# PCI_short_card_universal_-_32_BIT-4.net
KiCad netlist of a schematic drawn in Altium Designer
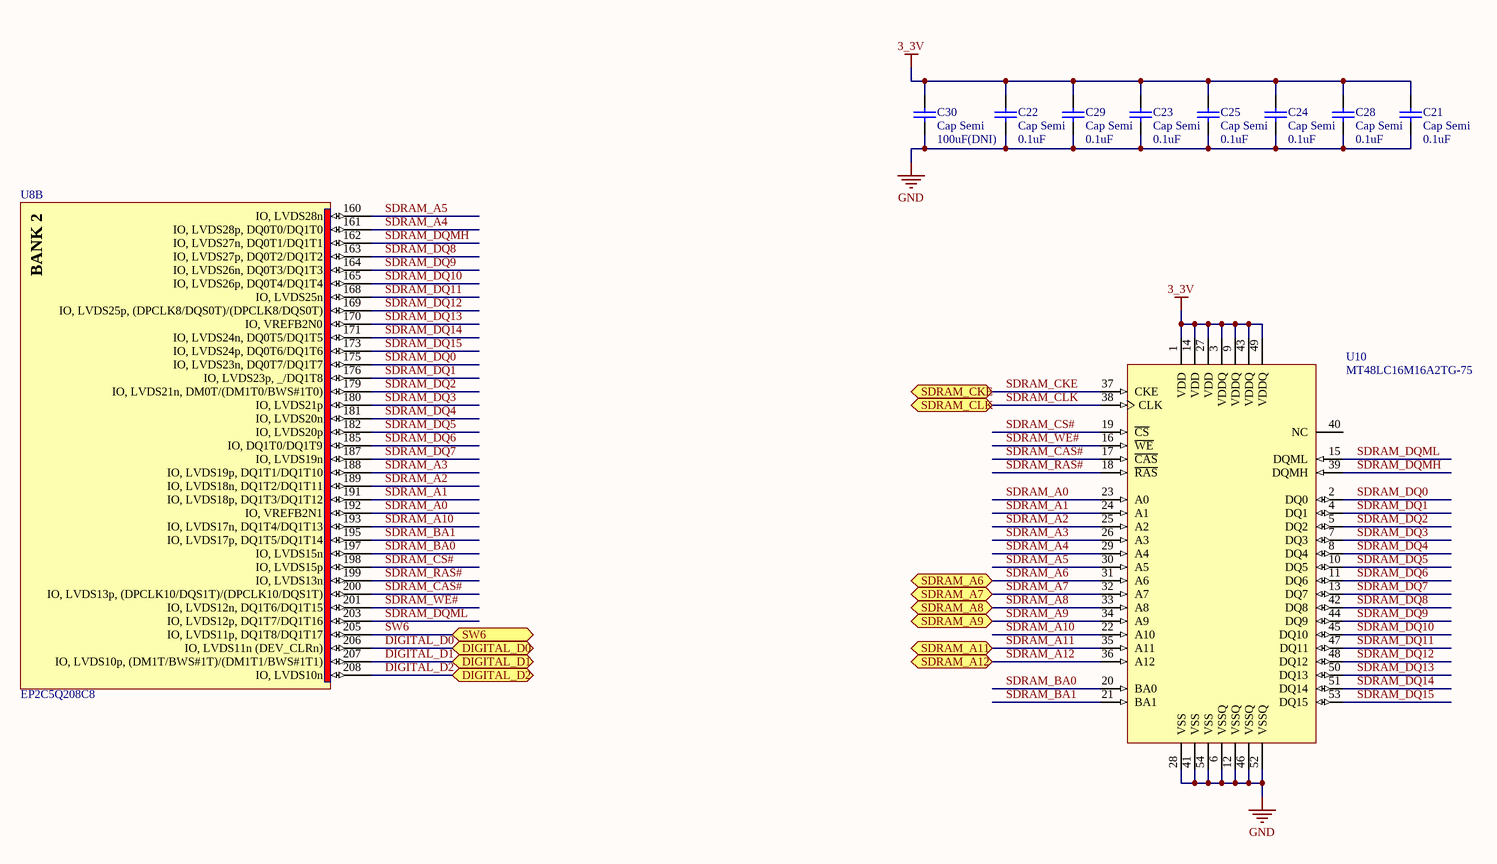
[diagram p0: PCI short card universal - 32 BIT-4.schdoc]

(export (version "E")
  (design (tool "Eeschema 10.0.6"))
  (components
    (comp (ref "C21")
      (value "Cap Semi")
      (footprint "RESC1608N")
      (description "Capacitor (Semiconductor SIM Model)")
      (fields (field (name "ALTIUM_VALUE") "0.1uF") (field (name "PUBLISHER") "Altium Limited"))
      (libsource (lib "Miscellaneous Devices") (part "Cap Semi"))
    )
    (comp (ref "C22")
      (value "Cap Semi")
      (footprint "RESC1608N")
      (description "Capacitor (Semiconductor SIM Model)")
      (fields (field (name "ALTIUM_VALUE") "0.1uF") (field (name "PUBLISHER") "Altium Limited"))
      (libsource (lib "Miscellaneous Devices") (part "Cap Semi"))
    )
    (comp (ref "C23")
      (value "Cap Semi")
      (footprint "RESC1608N")
      (description "Capacitor (Semiconductor SIM Model)")
      (fields (field (name "ALTIUM_VALUE") "0.1uF") (field (name "PUBLISHER") "Altium Limited"))
      (libsource (lib "Miscellaneous Devices") (part "Cap Semi"))
    )
    (comp (ref "C24")
      (value "Cap Semi")
      (footprint "RESC1608N")
      (description "Capacitor (Semiconductor SIM Model)")
      (fields (field (name "ALTIUM_VALUE") "0.1uF") (field (name "PUBLISHER") "Altium Limited"))
      (libsource (lib "Miscellaneous Devices") (part "Cap Semi"))
    )
    (comp (ref "C25")
      (value "Cap Semi")
      (footprint "RESC1608N")
      (description "Capacitor (Semiconductor SIM Model)")
      (fields (field (name "ALTIUM_VALUE") "0.1uF") (field (name "PUBLISHER") "Altium Limited"))
      (libsource (lib "Miscellaneous Devices") (part "Cap Semi"))
    )
    (comp (ref "C28")
      (value "Cap Semi")
      (footprint "RESC1608N")
      (description "Capacitor (Semiconductor SIM Model)")
      (fields (field (name "ALTIUM_VALUE") "0.1uF") (field (name "PUBLISHER") "Altium Limited"))
      (libsource (lib "Miscellaneous Devices") (part "Cap Semi"))
    )
    (comp (ref "C29")
      (value "Cap Semi")
      (footprint "RESC1608N")
      (description "Capacitor (Semiconductor SIM Model)")
      (fields (field (name "ALTIUM_VALUE") "0.1uF") (field (name "PUBLISHER") "Altium Limited"))
      (libsource (lib "Miscellaneous Devices") (part "Cap Semi"))
    )
    (comp (ref "C30")
      (value "Cap Semi")
      (footprint "CD3225-1210")
      (description "Capacitor (Semiconductor SIM Model)")
      (fields (field (name "ALTIUM_VALUE") "100uF(DNI)") (field (name "PUBLISHER") "Altium Limited"))
      (libsource (lib "Miscellaneous Devices") (part "Cap Semi"))
    )
    (comp (ref "U8")
      (value "EP2C5Q208C8")
      (footprint "PQFP208_N")
      (fields (field (name "PUBLISHER") "Altium Limited"))
      (libsource (lib "Altera Cyclone II") (part "EP2C5Q208C8"))
    )
    (comp (ref "U10")
      (value "MT48LC16M16A2TG-75")
      (footprint "TSOP2-54_M")
      (description "MICRON")
      (fields (field (name "PUBLISHER") "Altium Limited"))
      (libsource (lib "Micron Memory Dynamic RAM") (part "MT48LC16M16A2TG-75"))
    )
  )
  (nets
    (net (code "1") (name "/DIGITAL_D0") (class "Default")
      (node (ref "U8") (pin "206") (pinfunction "IO,_LVDS11n_(DEV_CLRn)_206") (pintype "bidirectional"))
    )
    (net (code "2") (name "/DIGITAL_D1") (class "Default")
      (node (ref "U8") (pin "207") (pinfunction "IO,_LVDS10p,_(DM1T/BWS#1T)/(DM1T1/BWS#1T1)_207") (pintype "bidirectional"))
    )
    (net (code "3") (name "/DIGITAL_D2") (class "Default")
      (node (ref "U8") (pin "208") (pinfunction "IO,_LVDS10n_208") (pintype "bidirectional"))
    )
    (net (code "4") (name "/SDRAM_A0") (class "Default")
      (node (ref "U10") (pin "23") (pinfunction "A0_23") (pintype "input"))
      (node (ref "U8") (pin "192") (pinfunction "IO,_VREFB2N1_192") (pintype "bidirectional"))
    )
    (net (code "5") (name "/SDRAM_A1") (class "Default")
      (node (ref "U10") (pin "24") (pinfunction "A1_24") (pintype "input"))
      (node (ref "U8") (pin "191") (pinfunction "IO,_LVDS18p,_DQ1T3/DQ1T12_191") (pintype "bidirectional"))
    )
    (net (code "6") (name "/SDRAM_A2") (class "Default")
      (node (ref "U10") (pin "25") (pinfunction "A2_25") (pintype "input"))
      (node (ref "U8") (pin "189") (pinfunction "IO,_LVDS18n,_DQ1T2/DQ1T11_189") (pintype "bidirectional"))
    )
    (net (code "7") (name "/SDRAM_A3") (class "Default")
      (node (ref "U10") (pin "26") (pinfunction "A3_26") (pintype "input"))
      (node (ref "U8") (pin "188") (pinfunction "IO,_LVDS19p,_DQ1T1/DQ1T10_188") (pintype "bidirectional"))
    )
    (net (code "8") (name "/SDRAM_A4") (class "Default")
      (node (ref "U10") (pin "29") (pinfunction "A4_29") (pintype "input"))
      (node (ref "U8") (pin "161") (pinfunction "IO,_LVDS28p,_DQ0T0/DQ1T0_161") (pintype "bidirectional"))
    )
    (net (code "9") (name "/SDRAM_A5") (class "Default")
      (node (ref "U10") (pin "30") (pinfunction "A5_30") (pintype "input"))
      (node (ref "U8") (pin "160") (pinfunction "IO,_LVDS28n_160") (pintype "bidirectional"))
    )
    (net (code "10") (name "/SDRAM_A6") (class "Default")
      (node (ref "U10") (pin "31") (pinfunction "A6_31") (pintype "input"))
    )
    (net (code "11") (name "/SDRAM_A7") (class "Default")
      (node (ref "U10") (pin "32") (pinfunction "A7_32") (pintype "input"))
    )
    (net (code "12") (name "/SDRAM_A8") (class "Default")
      (node (ref "U10") (pin "33") (pinfunction "A8_33") (pintype "input"))
    )
    (net (code "13") (name "/SDRAM_A9") (class "Default")
      (node (ref "U10") (pin "34") (pinfunction "A9_34") (pintype "input"))
    )
    (net (code "14") (name "/SDRAM_A10") (class "Default")
      (node (ref "U10") (pin "22") (pinfunction "A10_22") (pintype "input"))
      (node (ref "U8") (pin "193") (pinfunction "IO,_LVDS17n,_DQ1T4/DQ1T13_193") (pintype "bidirectional"))
    )
    (net (code "15") (name "/SDRAM_A11") (class "Default")
      (node (ref "U10") (pin "35") (pinfunction "A11_35") (pintype "input"))
    )
    (net (code "16") (name "/SDRAM_A12") (class "Default")
      (node (ref "U10") (pin "36") (pinfunction "A12_36") (pintype "input"))
    )
    (net (code "17") (name "/SDRAM_BA0") (class "Default")
      (node (ref "U10") (pin "20") (pinfunction "BA0_20") (pintype "input"))
      (node (ref "U8") (pin "197") (pinfunction "IO,_LVDS15n_197") (pintype "bidirectional"))
    )
    (net (code "18") (name "/SDRAM_BA1") (class "Default")
      (node (ref "U10") (pin "21") (pinfunction "BA1_21") (pintype "input"))
      (node (ref "U8") (pin "195") (pinfunction "IO,_LVDS17p,_DQ1T5/DQ1T14_195") (pintype "bidirectional"))
    )
    (net (code "19") (name "/SDRAM_CAS#") (class "Default")
      (node (ref "U10") (pin "17") (pinfunction "~{CAS}_17") (pintype "input"))
      (node (ref "U8") (pin "200") (pinfunction "IO,_LVDS13p,_(DPCLK10/DQS1T)/(DPCLK10/DQS1T)_200") (pintype "bidirectional"))
    )
    (net (code "20") (name "/SDRAM_CKE") (class "Default")
      (node (ref "U10") (pin "37") (pinfunction "CKE_37") (pintype "input"))
    )
    (net (code "21") (name "/SDRAM_CLK") (class "Default")
      (node (ref "U10") (pin "38") (pinfunction "CLK_38") (pintype "input"))
    )
    (net (code "22") (name "/SDRAM_CS#") (class "Default")
      (node (ref "U10") (pin "19") (pinfunction "~{CS}_19") (pintype "input"))
      (node (ref "U8") (pin "198") (pinfunction "IO,_LVDS15p_198") (pintype "bidirectional"))
    )
    (net (code "23") (name "/SDRAM_DQ0") (class "Default")
      (node (ref "U10") (pin "2") (pinfunction "DQ0_2") (pintype "bidirectional"))
      (node (ref "U8") (pin "175") (pinfunction "IO,_LVDS23n,_DQ0T7/DQ1T7_175") (pintype "bidirectional"))
    )
    (net (code "24") (name "/SDRAM_DQ1") (class "Default")
      (node (ref "U10") (pin "4") (pinfunction "DQ1_4") (pintype "bidirectional"))
      (node (ref "U8") (pin "176") (pinfunction "IO,_LVDS23p,__/DQ1T8_176") (pintype "bidirectional"))
    )
    (net (code "25") (name "/SDRAM_DQ2") (class "Default")
      (node (ref "U10") (pin "5") (pinfunction "DQ2_5") (pintype "bidirectional"))
      (node (ref "U8") (pin "179") (pinfunction "IO,_LVDS21n,_DM0T/(DM1T0/BWS#1T0)_179") (pintype "bidirectional"))
    )
    (net (code "26") (name "/SDRAM_DQ3") (class "Default")
      (node (ref "U10") (pin "7") (pinfunction "DQ3_7") (pintype "bidirectional"))
      (node (ref "U8") (pin "180") (pinfunction "IO,_LVDS21p_180") (pintype "bidirectional"))
    )
    (net (code "27") (name "/SDRAM_DQ4") (class "Default")
      (node (ref "U10") (pin "8") (pinfunction "DQ4_8") (pintype "bidirectional"))
      (node (ref "U8") (pin "181") (pinfunction "IO,_LVDS20n_181") (pintype "bidirectional"))
    )
    (net (code "28") (name "/SDRAM_DQ5") (class "Default")
      (node (ref "U10") (pin "10") (pinfunction "DQ5_10") (pintype "bidirectional"))
      (node (ref "U8") (pin "182") (pinfunction "IO,_LVDS20p_182") (pintype "bidirectional"))
    )
    (net (code "29") (name "/SDRAM_DQ6") (class "Default")
      (node (ref "U10") (pin "11") (pinfunction "DQ6_11") (pintype "bidirectional"))
      (node (ref "U8") (pin "185") (pinfunction "IO,_DQ1T0/DQ1T9_185") (pintype "bidirectional"))
    )
    (net (code "30") (name "/SDRAM_DQ7") (class "Default")
      (node (ref "U10") (pin "13") (pinfunction "DQ7_13") (pintype "bidirectional"))
      (node (ref "U8") (pin "187") (pinfunction "IO,_LVDS19n_187") (pintype "bidirectional"))
    )
    (net (code "31") (name "/SDRAM_DQ8") (class "Default")
      (node (ref "U10") (pin "42") (pinfunction "DQ8_42") (pintype "bidirectional"))
      (node (ref "U8") (pin "163") (pinfunction "IO,_LVDS27p,_DQ0T2/DQ1T2_163") (pintype "bidirectional"))
    )
    (net (code "32") (name "/SDRAM_DQ9") (class "Default")
      (node (ref "U10") (pin "44") (pinfunction "DQ9_44") (pintype "bidirectional"))
      (node (ref "U8") (pin "164") (pinfunction "IO,_LVDS26n,_DQ0T3/DQ1T3_164") (pintype "bidirectional"))
    )
    (net (code "33") (name "/SDRAM_DQ10") (class "Default")
      (node (ref "U10") (pin "45") (pinfunction "DQ10_45") (pintype "bidirectional"))
      (node (ref "U8") (pin "165") (pinfunction "IO,_LVDS26p,_DQ0T4/DQ1T4_165") (pintype "bidirectional"))
    )
    (net (code "34") (name "/SDRAM_DQ11") (class "Default")
      (node (ref "U10") (pin "47") (pinfunction "DQ11_47") (pintype "bidirectional"))
      (node (ref "U8") (pin "168") (pinfunction "IO,_LVDS25n_168") (pintype "bidirectional"))
    )
    (net (code "35") (name "/SDRAM_DQ12") (class "Default")
      (node (ref "U10") (pin "48") (pinfunction "DQ12_48") (pintype "bidirectional"))
      (node (ref "U8") (pin "169") (pinfunction "IO,_LVDS25p,_(DPCLK8/DQS0T)/(DPCLK8/DQS0T)_169") (pintype "bidirectional"))
    )
    (net (code "36") (name "/SDRAM_DQ13") (class "Default")
      (node (ref "U10") (pin "50") (pinfunction "DQ13_50") (pintype "bidirectional"))
      (node (ref "U8") (pin "170") (pinfunction "IO,_VREFB2N0_170") (pintype "bidirectional"))
    )
    (net (code "37") (name "/SDRAM_DQ14") (class "Default")
      (node (ref "U10") (pin "51") (pinfunction "DQ14_51") (pintype "bidirectional"))
      (node (ref "U8") (pin "171") (pinfunction "IO,_LVDS24n,_DQ0T5/DQ1T5_171") (pintype "bidirectional"))
    )
    (net (code "38") (name "/SDRAM_DQ15") (class "Default")
      (node (ref "U10") (pin "53") (pinfunction "DQ15_53") (pintype "bidirectional"))
      (node (ref "U8") (pin "173") (pinfunction "IO,_LVDS24p,_DQ0T6/DQ1T6_173") (pintype "bidirectional"))
    )
    (net (code "39") (name "/SDRAM_DQMH") (class "Default")
      (node (ref "U10") (pin "39") (pinfunction "DQMH_39") (pintype "input"))
      (node (ref "U8") (pin "162") (pinfunction "IO,_LVDS27n,_DQ0T1/DQ1T1_162") (pintype "bidirectional"))
    )
    (net (code "40") (name "/SDRAM_DQML") (class "Default")
      (node (ref "U10") (pin "15") (pinfunction "DQML_15") (pintype "input"))
      (node (ref "U8") (pin "203") (pinfunction "IO,_LVDS12p,_DQ1T7/DQ1T16_203") (pintype "bidirectional"))
    )
    (net (code "41") (name "/SDRAM_RAS#") (class "Default")
      (node (ref "U10") (pin "18") (pinfunction "~{RAS}_18") (pintype "input"))
      (node (ref "U8") (pin "199") (pinfunction "IO,_LVDS13n_199") (pintype "bidirectional"))
    )
    (net (code "42") (name "/SDRAM_WE#") (class "Default")
      (node (ref "U10") (pin "16") (pinfunction "~{WE}_16") (pintype "input"))
      (node (ref "U8") (pin "201") (pinfunction "IO,_LVDS12n,_DQ1T6/DQ1T15_201") (pintype "bidirectional"))
    )
    (net (code "43") (name "/SW6") (class "Default")
      (node (ref "U8") (pin "205") (pinfunction "IO,_LVDS11p,_DQ1T8/DQ1T17_205") (pintype "bidirectional"))
    )
    (net (code "44") (name "3_3V") (class "Default")
      (node (ref "C21") (pin "2") (pinfunction "2_2") (pintype "passive"))
      (node (ref "C22") (pin "2") (pinfunction "2_2") (pintype "passive"))
      (node (ref "C23") (pin "2") (pinfunction "2_2") (pintype "passive"))
      (node (ref "C24") (pin "2") (pinfunction "2_2") (pintype "passive"))
      (node (ref "C25") (pin "2") (pinfunction "2_2") (pintype "passive"))
      (node (ref "C28") (pin "2") (pinfunction "2_2") (pintype "passive"))
      (node (ref "C29") (pin "2") (pinfunction "2_2") (pintype "passive"))
      (node (ref "C30") (pin "2") (pinfunction "2_2") (pintype "passive"))
      (node (ref "U10") (pin "1") (pinfunction "VDD_1") (pintype "power_in"))
      (node (ref "U10") (pin "14") (pinfunction "VDD_14") (pintype "power_in"))
      (node (ref "U10") (pin "27") (pinfunction "VDD_27") (pintype "power_in"))
      (node (ref "U10") (pin "3") (pinfunction "VDDQ_3") (pintype "power_in"))
      (node (ref "U10") (pin "43") (pinfunction "VDDQ_43") (pintype "power_in"))
      (node (ref "U10") (pin "49") (pinfunction "VDDQ_49") (pintype "power_in"))
      (node (ref "U10") (pin "9") (pinfunction "VDDQ_9") (pintype "power_in"))
    )
    (net (code "45") (name "GND") (class "Default")
      (node (ref "C21") (pin "1") (pinfunction "1_1") (pintype "passive"))
      (node (ref "C22") (pin "1") (pinfunction "1_1") (pintype "passive"))
      (node (ref "C23") (pin "1") (pinfunction "1_1") (pintype "passive"))
      (node (ref "C24") (pin "1") (pinfunction "1_1") (pintype "passive"))
      (node (ref "C25") (pin "1") (pinfunction "1_1") (pintype "passive"))
      (node (ref "C28") (pin "1") (pinfunction "1_1") (pintype "passive"))
      (node (ref "C29") (pin "1") (pinfunction "1_1") (pintype "passive"))
      (node (ref "C30") (pin "1") (pinfunction "1_1") (pintype "passive"))
      (node (ref "U10") (pin "12") (pinfunction "VSSQ_12") (pintype "power_in"))
      (node (ref "U10") (pin "28") (pinfunction "VSS_28") (pintype "power_in"))
      (node (ref "U10") (pin "41") (pinfunction "VSS_41") (pintype "power_in"))
      (node (ref "U10") (pin "46") (pinfunction "VSSQ_46") (pintype "power_in"))
      (node (ref "U10") (pin "52") (pinfunction "VSSQ_52") (pintype "power_in"))
      (node (ref "U10") (pin "54") (pinfunction "VSS_54") (pintype "power_in"))
      (node (ref "U10") (pin "6") (pinfunction "VSSQ_6") (pintype "power_in"))
    )
    (net (code "46") (name "unconnected-(U10-NC-Pad40)") (class "Default")
      (node (ref "U10") (pin "40") (pinfunction "NC_40") (pintype "passive"))
    )
  )
)
